# Relay.net
KiCad netlist of a schematic drawn in Altium Designer
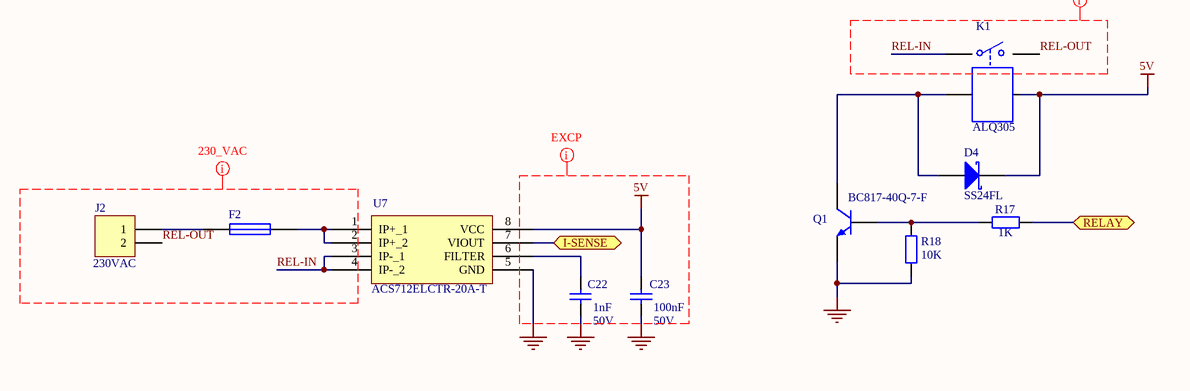
[diagram p0: Relay.SchDoc]

(export (version "E")
  (design (tool "Eeschema 10.0.6"))
  (components
    (comp (ref "C22")
      (value "Capacitor")
      (footprint "CAPC1608N")
      (fields
        (field (name "PART NUMBER") "CAP-000000010")
        (field (name "VALUE 1") "1nF")
        (field (name "VALUE 2") "50V")
      )
      (libsource (lib "ESP32-Relay-Module") (part "Capacitor"))
    )
    (comp (ref "C23")
      (value "Capacitor")
      (footprint "CAPC1608N")
      (fields
        (field (name "PART NUMBER") "CAP-000000002")
        (field (name "VALUE 1") "100nF")
        (field (name "VALUE 2") "50V")
      )
      (libsource (lib "ESP32-Relay-Module") (part "Capacitor"))
    )
    (comp (ref "D4")
      (value "SS24FL")
      (footprint "SOD-123F")
      (fields (field (name "PART NUMBER") "DIS-000000002"))
      (libsource (lib "ESP32-Relay-Module") (part "DSchottky"))
    )
    (comp (ref "F2")
      (value "0031.8001")
      (footprint "SCHURTER_0031.8201")
      (fields (field (name "PART NUMBER") "FUS-000000001"))
      (libsource (lib "ESP32-Relay-Module") (part "Fuse"))
    )
    (comp (ref "J2")
      (value "230VAC")
      (footprint "CUI_TB007-508-02BE")
      (fields (field (name "PART NUMBER") "CON-000000001"))
      (libsource (lib "ESP32-Relay-Module") (part "Header 2"))
    )
    (comp (ref "K1")
      (value "ALQ305")
      (footprint "ALQ305")
      (fields (field (name "PART NUMBER") "SWC-000000003"))
      (libsource (lib "ESP32-Relay-Module") (part "ALQ305"))
    )
    (comp (ref "Q1")
      (value "BC817-40Q-7-F")
      (footprint "SOT23-3N")
      (fields (field (name "PART NUMBER") "TRP-000000001"))
      (libsource (lib "ESP32-Relay-Module") (part "NPN1"))
    )
    (comp (ref "R17")
      (value "Resistor")
      (footprint "RESC1608N")
      (fields (field (name "PART NUMBER") "RES-000000006") (field (name "VALUE 1") "1K"))
      (libsource (lib "") (part "Resistor_1"))
    )
    (comp (ref "R18")
      (value "Resistor")
      (footprint "RESC1608N")
      (fields (field (name "PART NUMBER") "RES-000000001") (field (name "VALUE 1") "10K"))
      (libsource (lib "ESP32-Relay-Module") (part "Resistor"))
    )
    (comp (ref "U7")
      (value "ACS712ELCTR-20A-T")
      (footprint "SOIC127P600X175-8N")
      (fields (field (name "PART NUMBER") "SEN-000000001"))
      (libsource (lib "ESP32-Relay-Module") (part "ACS712ELCTR-20A-T"))
    )
  )
  (nets
    (net (code "1") (name "/I-SENSE") (class "Default")
      (node (ref "U7") (pin "7") (pinfunction "VIOUT_7") (pintype "passive"))
    )
    (net (code "2") (name "/REL-IN") (class "Default")
      (node (ref "K1") (pin "3") (pinfunction "COM_3") (pintype "passive"))
      (node (ref "U7") (pin "3") (pinfunction "IP-_1_3") (pintype "passive"))
      (node (ref "U7") (pin "4") (pinfunction "IP-_2_4") (pintype "passive"))
    )
    (net (code "3") (name "/REL-OUT") (class "Default")
      (node (ref "J2") (pin "2") (pinfunction "2_2") (pintype "passive"))
      (node (ref "K1") (pin "2") (pinfunction "NO_2") (pintype "passive"))
    )
    (net (code "4") (name "/RELAY") (class "Default")
      (node (ref "R17") (pin "2") (pinfunction "2_2") (pintype "passive"))
    )
    (net (code "5") (name "5V") (class "Default")
      (node (ref "C23") (pin "2") (pinfunction "2_2") (pintype "passive"))
      (node (ref "D4") (pin "2") (pinfunction "K_2") (pintype "passive"))
      (node (ref "K1") (pin "1") (pinfunction "COIL_1_1") (pintype "passive"))
      (node (ref "U7") (pin "8") (pinfunction "VCC_8") (pintype "passive"))
    )
    (net (code "6") (name "GND") (class "Default")
      (node (ref "C22") (pin "1") (pinfunction "1_1") (pintype "passive"))
      (node (ref "C23") (pin "1") (pinfunction "1_1") (pintype "passive"))
      (node (ref "Q1") (pin "3") (pinfunction "E_3") (pintype "passive"))
      (node (ref "R18") (pin "1") (pinfunction "1_1") (pintype "passive"))
      (node (ref "U7") (pin "5") (pinfunction "GND_5") (pintype "passive"))
    )
    (net (code "7") (name "Net-(D4-A)") (class "Default")
      (node (ref "D4") (pin "1") (pinfunction "A_1") (pintype "passive"))
      (node (ref "K1") (pin "4") (pinfunction "COIL_2_4") (pintype "passive"))
      (node (ref "Q1") (pin "2") (pinfunction "C_2") (pintype "passive"))
    )
    (net (code "8") (name "Net-(F2-Pad1)") (class "Default")
      (node (ref "F2") (pin "1") (pinfunction "1_1") (pintype "passive"))
      (node (ref "J2") (pin "1") (pinfunction "1_1") (pintype "passive"))
    )
    (net (code "9") (name "Net-(Q1-B)") (class "Default")
      (node (ref "Q1") (pin "1") (pinfunction "B_1") (pintype "passive"))
      (node (ref "R17") (pin "1") (pinfunction "1_1") (pintype "passive"))
      (node (ref "R18") (pin "2") (pinfunction "2_2") (pintype "passive"))
    )
    (net (code "10") (name "Net-(U7-FILTER)") (class "Default")
      (node (ref "C22") (pin "2") (pinfunction "2_2") (pintype "passive"))
      (node (ref "U7") (pin "6") (pinfunction "FILTER_6") (pintype "passive"))
    )
    (net (code "11") (name "Net-(U7-IP+_1)") (class "Default")
      (node (ref "F2") (pin "2") (pinfunction "2_2") (pintype "passive"))
      (node (ref "U7") (pin "1") (pinfunction "IP+_1_1") (pintype "passive"))
      (node (ref "U7") (pin "2") (pinfunction "IP+_2_2") (pintype "passive"))
    )
  )
)
